# PAC.net
KiCad netlist of a schematic drawn in EAGLE
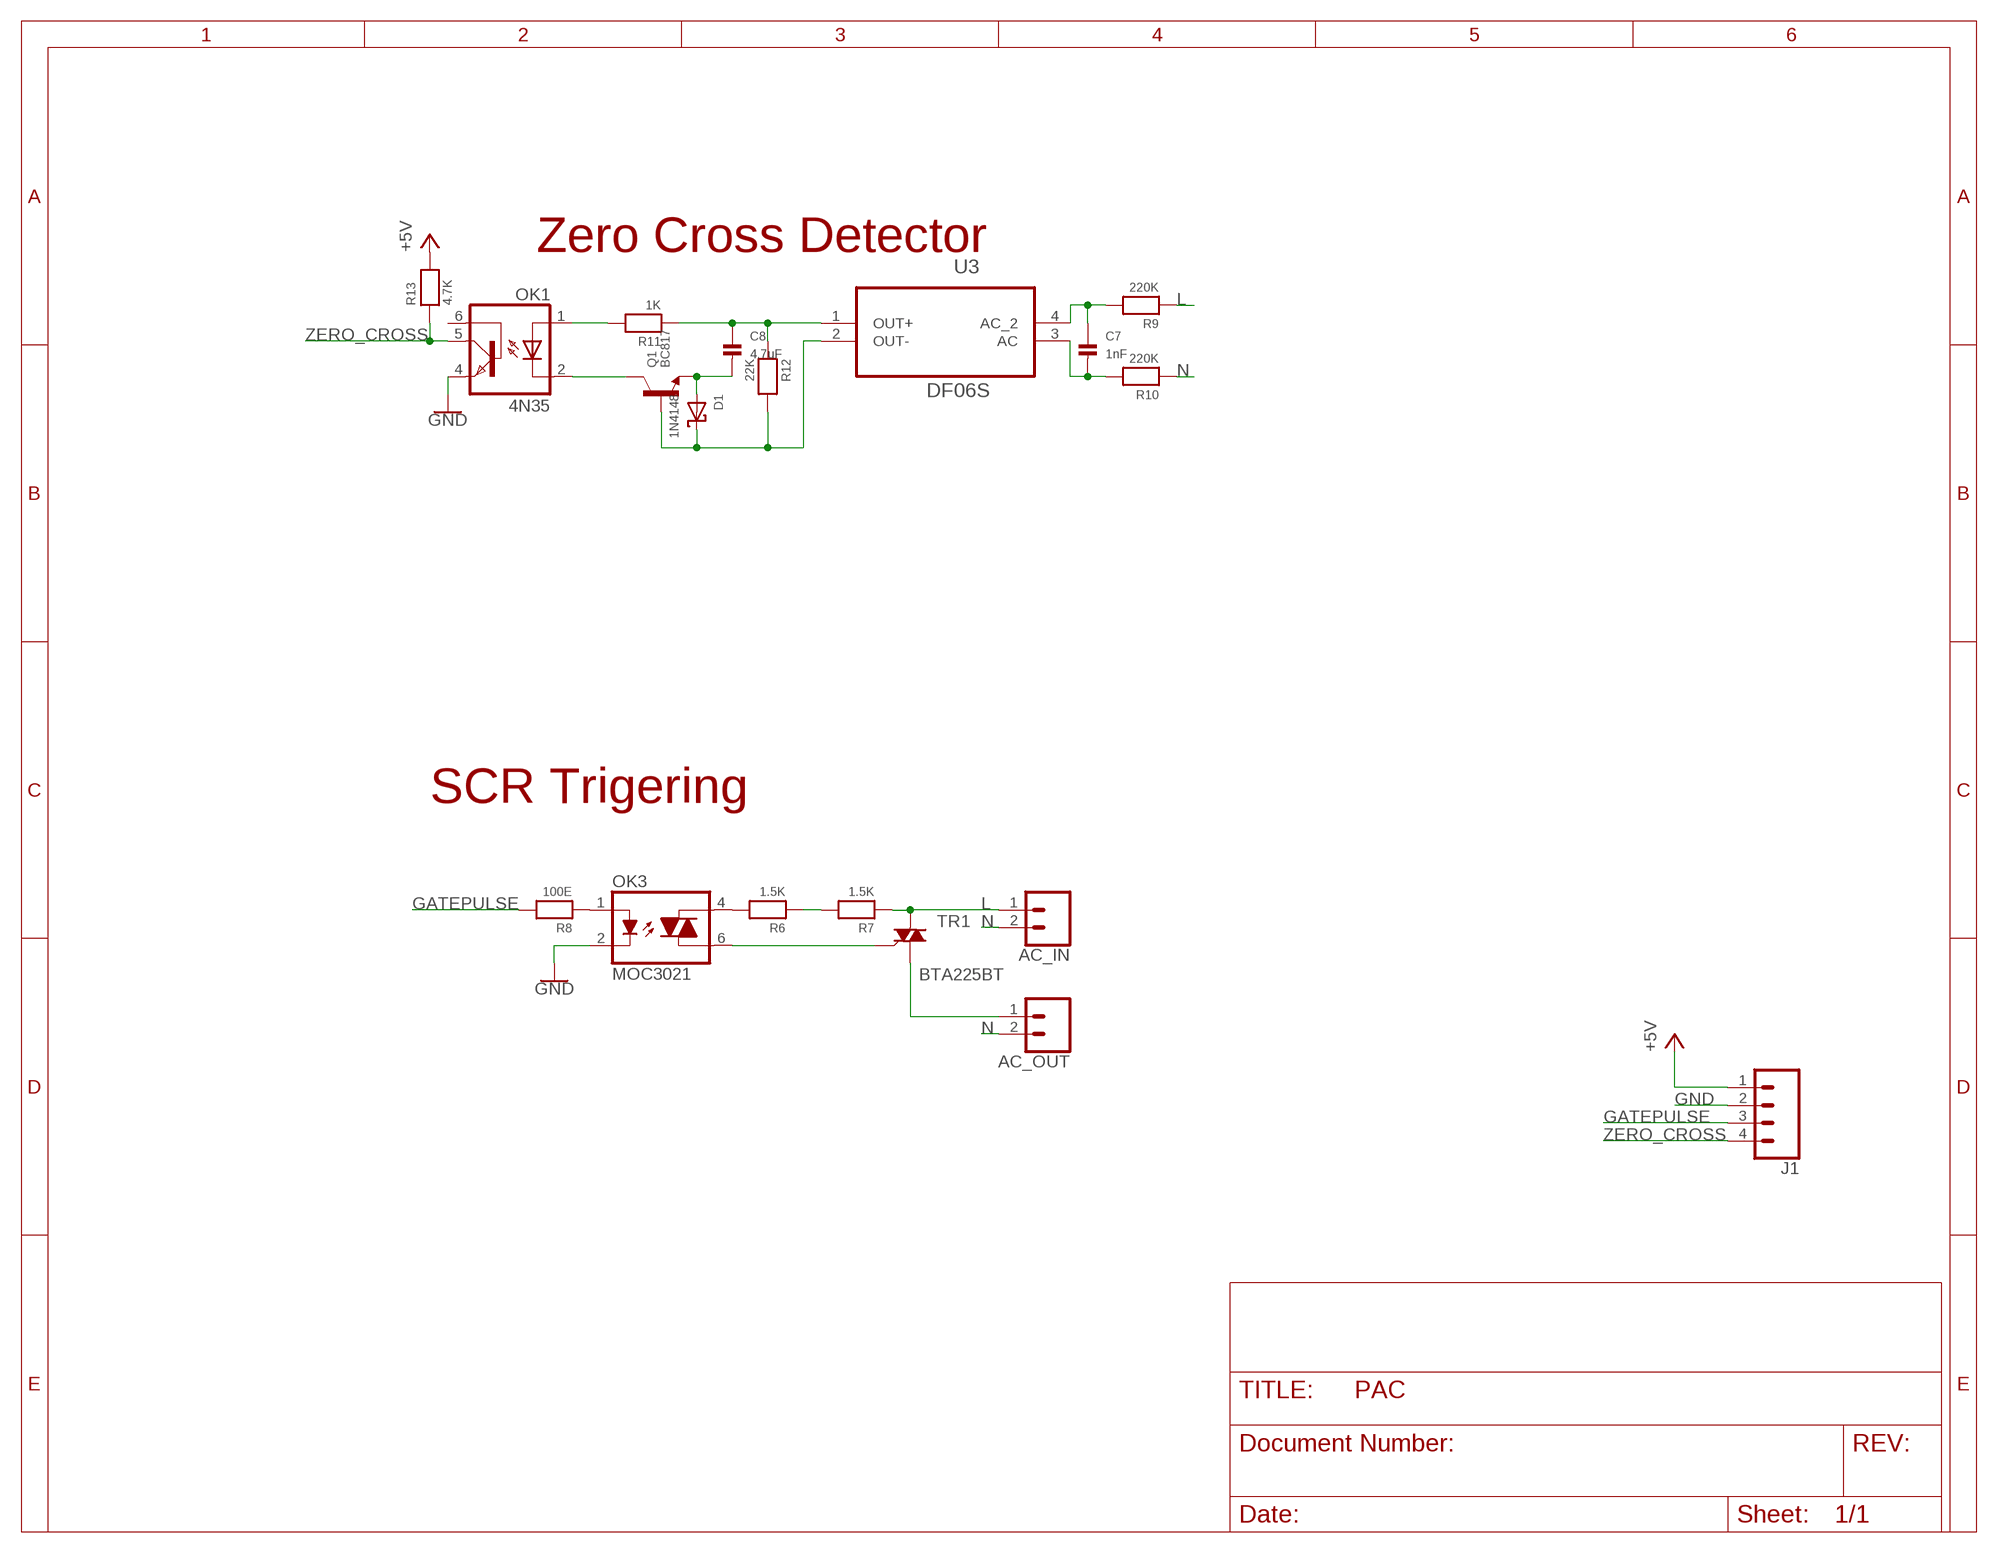
[diagram p0: schematic, sheet 1]

(export (version "E")
  (design (tool "Eeschema 10.0.6"))
  (components
    (comp (ref "AC_IN")
      (value "CONN_025MM")
      (footprint "eagle-import:SCREWTERMINAL-5MM-2")
      (libsource (lib "eagle-import") (part "CONN_025MM"))
    )
    (comp (ref "AC_OUT")
      (value "CONN_025MM")
      (footprint "eagle-import:SCREWTERMINAL-5MM-2")
      (libsource (lib "eagle-import") (part "CONN_025MM"))
    )
    (comp (ref "C7")
      (value "1nF")
      (footprint "eagle-import:1206")
      (fields (field (name "MF") "YAGEO") (field (name "MPN") "CC1206KKX7RBBB102"))
      (libsource (lib "eagle-import") (part "CAP_CERAMIC1206"))
    )
    (comp (ref "C8")
      (value "4.7uF")
      (footprint "eagle-import:1206")
      (fields (field (name "MF") "YAGEO") (field (name "MPN") "CC1206KKX7RBBB102"))
      (libsource (lib "eagle-import") (part "CAP_CERAMIC1206"))
    )
    (comp (ref "D1")
      (value "1N4148")
      (footprint "eagle-import:SOD-123")
      (fields (field (name "MF") "MULTICOMP") (field (name "MPN") "1N4148W-7-F"))
      (libsource (lib "eagle-import") (part "DIODESOD-123"))
    )
    (comp (ref "J1")
      (value "CONN_04POLAR")
      (footprint "eagle-import:MOLEX-1X4")
      (libsource (lib "eagle-import") (part "CONN_04POLAR"))
    )
    (comp (ref "OK1")
      (value "4N35")
      (footprint "eagle-import:DIL06")
      (fields
        (field (name "MF") "Vishay Semiconductor")
        (field (name "MF_1") "ON SEMICONDUCTOR")
        (field (name "MPN") "4N35SR2M")
      )
      (libsource (lib "eagle-import") (part "4N35"))
    )
    (comp (ref "OK3")
      (value "MOC3021")
      (footprint "eagle-import:DIL06")
      (fields (field (name "MF") "ON SEMICONDUCTOR") (field (name "MPN") "MOC3021SR2VM"))
      (libsource (lib "eagle-import") (part "MOC3021"))
    )
    (comp (ref "Q1")
      (value "BC817")
      (footprint "eagle-import:SOT23-W")
      (fields (field (name "MF") "MICRO COMMERCIAL COMPONENTS") (field (name "MPN") "BC817-40-TP"))
      (libsource (lib "eagle-import") (part "TRANSISTOR_NPNWAVE"))
    )
    (comp (ref "R6")
      (value "1.5K")
      (footprint "eagle-import:1206")
      (fields (field (name "MF") "TE CONNECTIVITY") (field (name "MPN") "CRGH1206F330R"))
      (libsource (lib "eagle-import") (part "RESISTOR1206"))
    )
    (comp (ref "R7")
      (value "1.5K")
      (footprint "eagle-import:1206")
      (fields (field (name "MF") "TE CONNECTIVITY") (field (name "MPN") "CRGH1206F330R"))
      (libsource (lib "eagle-import") (part "RESISTOR1206"))
    )
    (comp (ref "R8")
      (value "100E")
      (footprint "eagle-import:0805")
      (fields (field (name "MF") "VISHAY") (field (name "MPN") "CRCW0805100RFKEB"))
      (libsource (lib "eagle-import") (part "RESISTOR0805"))
    )
    (comp (ref "R9")
      (value "220K")
      (footprint "eagle-import:1206")
      (fields (field (name "MF") "MULTICOMP") (field (name "MPN") "MCWF12P2203FTL"))
      (libsource (lib "eagle-import") (part "RESISTOR1206"))
    )
    (comp (ref "R10")
      (value "220K")
      (footprint "eagle-import:1206")
      (fields (field (name "MF") "MULTICOMP") (field (name "MPN") "MCWF12P2203FTL"))
      (libsource (lib "eagle-import") (part "RESISTOR1206"))
    )
    (comp (ref "R11")
      (value "1K")
      (footprint "eagle-import:0805")
      (fields (field (name "MF") "VISHAY") (field (name "MPN") "CRCW08051K00JNEA"))
      (libsource (lib "eagle-import") (part "RESISTOR0805"))
    )
    (comp (ref "R12")
      (value "22K")
      (footprint "eagle-import:0805")
      (fields (field (name "MF") "YAGEO") (field (name "MPN") "RC0805JR-0722KL"))
      (libsource (lib "eagle-import") (part "RESISTOR0805"))
    )
    (comp (ref "R13")
      (value "4.7K")
      (footprint "eagle-import:0805")
      (fields (field (name "MF") "PANASONIC ELECTRONIC COMPONENTS") (field (name "MPN") "ERJ-P06J472V"))
      (libsource (lib "eagle-import") (part "RESISTOR0805"))
    )
    (comp (ref "TR1")
      (value "BTA225BT")
      (footprint "eagle-import:TO220DS")
      (fields (field (name "MF") "STMICROELECTRONICS") (field (name "MPN") "BTA16-800CWRG"))
      (libsource (lib "eagle-import") (part "BTA225BT"))
    )
    (comp (ref "U3")
      (value "DF06S")
      (footprint "eagle-import:SOT508P985X260-4N")
      (fields (field (name "MF") "ON Semiconductor") (field (name "MF_1") "ON SEMICONDUCTOR"))
      (libsource (lib "eagle-import") (part "DF06S"))
    )
  )
  (nets
    (net (code "1") (name "+5V") (class "Default")
      (node (ref "J1") (pin "1") (pinfunction "1_1") (pintype "passive"))
      (node (ref "R13") (pin "2") (pinfunction "2_2") (pintype "passive"))
    )
    (net (code "2") (name "/GATEPULSE") (class "Default")
      (node (ref "J1") (pin "3") (pinfunction "3_3") (pintype "passive"))
      (node (ref "R8") (pin "2") (pinfunction "2_2") (pintype "passive"))
    )
    (net (code "3") (name "/L") (class "Default")
      (node (ref "AC_IN") (pin "1") (pinfunction "1_1") (pintype "passive"))
      (node (ref "R7") (pin "1") (pinfunction "1_1") (pintype "passive"))
      (node (ref "R9") (pin "1") (pinfunction "1_1") (pintype "passive"))
      (node (ref "TR1") (pin "A2") (pinfunction "A2_A2") (pintype "passive"))
    )
    (net (code "4") (name "/N") (class "Default")
      (node (ref "AC_IN") (pin "2") (pinfunction "2_2") (pintype "passive"))
      (node (ref "AC_OUT") (pin "2") (pinfunction "2_2") (pintype "passive"))
      (node (ref "R10") (pin "1") (pinfunction "1_1") (pintype "passive"))
    )
    (net (code "5") (name "/ZERO_CROSS") (class "Default")
      (node (ref "J1") (pin "4") (pinfunction "4_4") (pintype "passive"))
      (node (ref "OK1") (pin "5") (pinfunction "COL_5") (pintype "passive"))
      (node (ref "R13") (pin "1") (pinfunction "1_1") (pintype "passive"))
    )
    (net (code "6") (name "GND") (class "Default")
      (node (ref "J1") (pin "2") (pinfunction "2_2") (pintype "passive"))
      (node (ref "OK1") (pin "4") (pinfunction "EMI_4") (pintype "passive"))
      (node (ref "OK3") (pin "2") (pinfunction "C_2") (pintype "passive"))
    )
    (net (code "7") (name "Net-(AC_OUT-Pad1)") (class "Default")
      (node (ref "AC_OUT") (pin "1") (pinfunction "1_1") (pintype "passive"))
      (node (ref "TR1") (pin "A1") (pinfunction "A1_A1") (pintype "passive"))
    )
    (net (code "8") (name "Net-(C7-P$1)") (class "Default")
      (node (ref "C7") (pin "1") (pinfunction "P$1_1") (pintype "passive"))
      (node (ref "R9") (pin "2") (pinfunction "2_2") (pintype "passive"))
      (node (ref "U3") (pin "4") (pinfunction "AC_2_4") (pintype "input"))
    )
    (net (code "9") (name "Net-(C7-P$2)") (class "Default")
      (node (ref "C7") (pin "2") (pinfunction "P$2_2") (pintype "passive"))
      (node (ref "R10") (pin "2") (pinfunction "2_2") (pintype "passive"))
      (node (ref "U3") (pin "3") (pinfunction "AC_3") (pintype "input"))
    )
    (net (code "10") (name "Net-(C8-P$1)") (class "Default")
      (node (ref "C8") (pin "1") (pinfunction "P$1_1") (pintype "passive"))
      (node (ref "R11") (pin "1") (pinfunction "1_1") (pintype "passive"))
      (node (ref "R12") (pin "1") (pinfunction "1_1") (pintype "passive"))
      (node (ref "U3") (pin "1") (pinfunction "OUT+_1") (pintype "output"))
    )
    (net (code "11") (name "Net-(C8-P$2)") (class "Default")
      (node (ref "C8") (pin "2") (pinfunction "P$2_2") (pintype "passive"))
      (node (ref "D1") (pin "A") (pinfunction "A_A") (pintype "passive"))
      (node (ref "Q1") (pin "2") (pinfunction "E_2") (pintype "passive"))
    )
    (net (code "12") (name "Net-(OK1-A)") (class "Default")
      (node (ref "OK1") (pin "1") (pinfunction "A_1") (pintype "passive"))
      (node (ref "R11") (pin "2") (pinfunction "2_2") (pintype "passive"))
    )
    (net (code "13") (name "Net-(OK1-C)") (class "Default")
      (node (ref "OK1") (pin "2") (pinfunction "C_2") (pintype "passive"))
      (node (ref "Q1") (pin "3") (pinfunction "C_3") (pintype "passive"))
    )
    (net (code "14") (name "Net-(OK3-A)") (class "Default")
      (node (ref "OK3") (pin "1") (pinfunction "A_1") (pintype "passive"))
      (node (ref "R8") (pin "1") (pinfunction "1_1") (pintype "passive"))
    )
    (net (code "15") (name "Net-(OK3-A1)") (class "Default")
      (node (ref "OK3") (pin "6") (pinfunction "A1_6") (pintype "passive"))
      (node (ref "TR1") (pin "G") (pinfunction "G_G") (pintype "passive"))
    )
    (net (code "16") (name "Net-(OK3-A2)") (class "Default")
      (node (ref "OK3") (pin "4") (pinfunction "A2_4") (pintype "passive"))
      (node (ref "R6") (pin "2") (pinfunction "2_2") (pintype "passive"))
    )
    (net (code "17") (name "Net-(Q1-B)") (class "Default")
      (node (ref "D1") (pin "C") (pinfunction "C_C") (pintype "passive"))
      (node (ref "Q1") (pin "1") (pinfunction "B_1") (pintype "passive"))
      (node (ref "R12") (pin "2") (pinfunction "2_2") (pintype "passive"))
      (node (ref "U3") (pin "2") (pinfunction "OUT-_2") (pintype "output"))
    )
    (net (code "18") (name "Net-(R6-Pad1)") (class "Default")
      (node (ref "R6") (pin "1") (pinfunction "1_1") (pintype "passive"))
      (node (ref "R7") (pin "2") (pinfunction "2_2") (pintype "passive"))
    )
    (net (code "19") (name "unconnected-(OK1-BAS-Pad6)") (class "Default")
      (node (ref "OK1") (pin "6") (pinfunction "BAS_6") (pintype "passive"))
    )
  )
)
